# ESP32_WROOM32_E-DA_Sensor_Network_V1_0.net
KiCad netlist of a schematic drawn in EAGLE
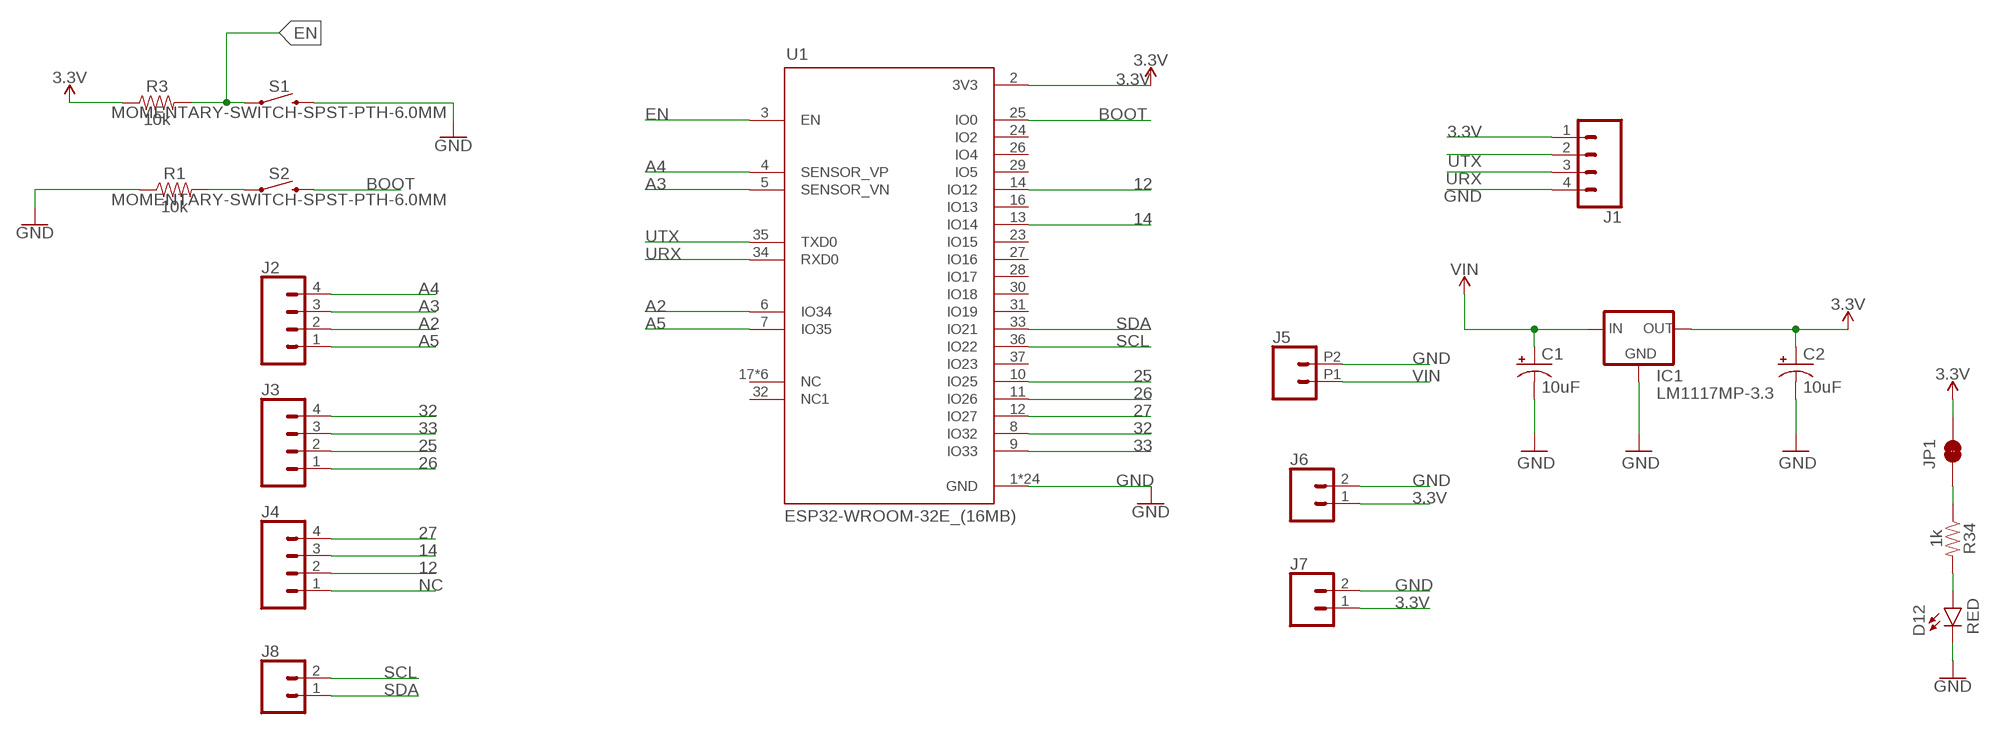
[diagram p0: schematic, sheet 1]

(export (version "E")
  (design (tool "Eeschema 10.0.6"))
  (components
    (comp (ref "C1")
      (value "10uF")
      (footprint "eagle-import:EIA3216")
      (libsource (lib "eagle-import") (part "10UF-TANT"))
    )
    (comp (ref "C2")
      (value "10uF")
      (footprint "eagle-import:EIA3216")
      (libsource (lib "eagle-import") (part "10UF-TANT"))
    )
    (comp (ref "D12")
      (value "RED")
      (footprint "eagle-import:LED-0603")
      (libsource (lib "eagle-import") (part "LED-RED0603"))
    )
    (comp (ref "IC1")
      (value "LM1117MP-3.3")
      (footprint "eagle-import:SOT223")
      (fields (field (name "MF") "Texas Instruments"))
      (libsource (lib "eagle-import") (part "LM1117?-MP3.3"))
    )
    (comp (ref "J1")
      (value "CONN_04")
      (footprint "eagle-import:1X04")
      (libsource (lib "eagle-import") (part "CONN_04"))
    )
    (comp (ref "J2")
      (value "CONN_04")
      (footprint "eagle-import:1X04")
      (libsource (lib "eagle-import") (part "CONN_04"))
    )
    (comp (ref "J3")
      (value "CONN_04")
      (footprint "eagle-import:1X04")
      (libsource (lib "eagle-import") (part "CONN_04"))
    )
    (comp (ref "J4")
      (value "CONN_04")
      (footprint "eagle-import:1X04")
      (libsource (lib "eagle-import") (part "CONN_04"))
    )
    (comp (ref "J5")
      (value "CONN_022.54MM_SCREWTERM")
      (footprint "eagle-import:1X02_2.54_SCREWTERM")
      (libsource (lib "eagle-import") (part "CONN_022.54MM_SCREWTERM"))
    )
    (comp (ref "J6")
      (value "CONN_021X02_NO_SILK")
      (footprint "eagle-import:1X02_NO_SILK")
      (libsource (lib "eagle-import") (part "CONN_021X02_NO_SILK"))
    )
    (comp (ref "J7")
      (value "CONN_021X02_NO_SILK")
      (footprint "eagle-import:1X02_NO_SILK")
      (libsource (lib "eagle-import") (part "CONN_021X02_NO_SILK"))
    )
    (comp (ref "J8")
      (value "CONN_02")
      (footprint "eagle-import:1X02")
      (libsource (lib "eagle-import") (part "CONN_02"))
    )
    (comp (ref "JP1")
      (value "JUMPER-SMT_2_NC_TRACE_SILK")
      (footprint "eagle-import:SMT-JUMPER_2_NC_TRACE_SILK")
      (libsource (lib "eagle-import") (part "JUMPER-SMT_2_NC_TRACE_SILK"))
    )
    (comp (ref "R1")
      (value "10k")
      (footprint "eagle-import:0603")
      (libsource (lib "eagle-import") (part "10KOHM-0603-1/10W-1%"))
    )
    (comp (ref "R3")
      (value "10k")
      (footprint "eagle-import:0603")
      (libsource (lib "eagle-import") (part "10KOHM-0603-1/10W-1%"))
    )
    (comp (ref "R34")
      (value "1k")
      (footprint "eagle-import:0402-TIGHT")
      (libsource (lib "eagle-import") (part "1KOHM-0402T-1/16W-1%"))
    )
    (comp (ref "S1")
      (value "MOMENTARY-SWITCH-SPST-PTH-6.0MM")
      (footprint "eagle-import:TACTILE_SWITCH_PTH_6.0MM")
      (libsource (lib "eagle-import") (part "MOMENTARY-SWITCH-SPST-PTH-6.0MM"))
    )
    (comp (ref "S2")
      (value "MOMENTARY-SWITCH-SPST-PTH-6.0MM")
      (footprint "eagle-import:TACTILE_SWITCH_PTH_6.0MM")
      (libsource (lib "eagle-import") (part "MOMENTARY-SWITCH-SPST-PTH-6.0MM"))
    )
    (comp (ref "U1")
      (value "ESP32-WROOM-32E_(16MB)")
      (footprint "eagle-import:MODULE_ESP32-WROOM-32E_(16MB)")
      (fields (field (name "MF") "Espressif Systems") (field (name "MP") "ESP32-WROOM-32E (16MB)"))
      (libsource (lib "eagle-import") (part "ESP32-WROOM-32E_(16MB)"))
    )
  )
  (nets
    (net (code "1") (name "/12") (class "Default")
      (node (ref "J4") (pin "2") (pinfunction "2_2") (pintype "passive"))
      (node (ref "U1") (pin "14") (pinfunction "IO12_14") (pintype "bidirectional"))
    )
    (net (code "2") (name "/14") (class "Default")
      (node (ref "J4") (pin "3") (pinfunction "3_3") (pintype "passive"))
      (node (ref "U1") (pin "13") (pinfunction "IO14_13") (pintype "bidirectional"))
    )
    (net (code "3") (name "/25") (class "Default")
      (node (ref "J3") (pin "2") (pinfunction "2_2") (pintype "passive"))
      (node (ref "U1") (pin "10") (pinfunction "IO25_10") (pintype "bidirectional"))
    )
    (net (code "4") (name "/26") (class "Default")
      (node (ref "J3") (pin "1") (pinfunction "1_1") (pintype "passive"))
      (node (ref "U1") (pin "11") (pinfunction "IO26_11") (pintype "bidirectional"))
    )
    (net (code "5") (name "/27") (class "Default")
      (node (ref "J4") (pin "4") (pinfunction "4_4") (pintype "passive"))
      (node (ref "U1") (pin "12") (pinfunction "IO27_12") (pintype "bidirectional"))
    )
    (net (code "6") (name "/32") (class "Default")
      (node (ref "J3") (pin "4") (pinfunction "4_4") (pintype "passive"))
      (node (ref "U1") (pin "8") (pinfunction "IO32_8") (pintype "bidirectional"))
    )
    (net (code "7") (name "/33") (class "Default")
      (node (ref "J3") (pin "3") (pinfunction "3_3") (pintype "passive"))
      (node (ref "U1") (pin "9") (pinfunction "IO33_9") (pintype "bidirectional"))
    )
    (net (code "8") (name "/A2") (class "Default")
      (node (ref "J2") (pin "2") (pinfunction "2_2") (pintype "passive"))
      (node (ref "U1") (pin "6") (pinfunction "IO34_6") (pintype "input"))
    )
    (net (code "9") (name "/A3") (class "Default")
      (node (ref "J2") (pin "3") (pinfunction "3_3") (pintype "passive"))
      (node (ref "U1") (pin "5") (pinfunction "SENSOR_VN_5") (pintype "input"))
    )
    (net (code "10") (name "/A4") (class "Default")
      (node (ref "J2") (pin "4") (pinfunction "4_4") (pintype "passive"))
      (node (ref "U1") (pin "4") (pinfunction "SENSOR_VP_4") (pintype "input"))
    )
    (net (code "11") (name "/A5") (class "Default")
      (node (ref "J2") (pin "1") (pinfunction "1_1") (pintype "passive"))
      (node (ref "U1") (pin "7") (pinfunction "IO35_7") (pintype "input"))
    )
    (net (code "12") (name "/BOOT") (class "Default")
      (node (ref "S2") (pin "3") (pinfunction "2_3") (pintype "passive"))
      (node (ref "U1") (pin "25") (pinfunction "IO0_25") (pintype "bidirectional"))
    )
    (net (code "13") (name "/NC") (class "Default")
      (node (ref "J4") (pin "1") (pinfunction "1_1") (pintype "passive"))
    )
    (net (code "14") (name "/SCL") (class "Default")
      (node (ref "J8") (pin "2") (pinfunction "2_2") (pintype "passive"))
      (node (ref "U1") (pin "36") (pinfunction "IO22_36") (pintype "bidirectional"))
    )
    (net (code "15") (name "/SDA") (class "Default")
      (node (ref "J8") (pin "1") (pinfunction "1_1") (pintype "passive"))
      (node (ref "U1") (pin "33") (pinfunction "IO21_33") (pintype "bidirectional"))
    )
    (net (code "16") (name "/URX") (class "Default")
      (node (ref "J1") (pin "3") (pinfunction "3_3") (pintype "passive"))
      (node (ref "U1") (pin "34") (pinfunction "RXD0_34") (pintype "bidirectional"))
    )
    (net (code "17") (name "/UTX") (class "Default")
      (node (ref "J1") (pin "2") (pinfunction "2_2") (pintype "passive"))
      (node (ref "U1") (pin "35") (pinfunction "TXD0_35") (pintype "bidirectional"))
    )
    (net (code "18") (name "3.3V") (class "Default")
      (node (ref "C2") (pin "A") (pinfunction "+_A") (pintype "passive"))
      (node (ref "IC1") (pin "2") (pinfunction "OUT_2") (pintype "passive"))
      (node (ref "IC1") (pin "4") (pinfunction "OUT_4") (pintype "passive"))
      (node (ref "J1") (pin "1") (pinfunction "1_1") (pintype "passive"))
      (node (ref "J6") (pin "1") (pinfunction "1_1") (pintype "passive"))
      (node (ref "J7") (pin "1") (pinfunction "1_1") (pintype "passive"))
      (node (ref "JP1") (pin "2") (pinfunction "2_2") (pintype "passive"))
      (node (ref "R3") (pin "1") (pinfunction "1_1") (pintype "passive"))
      (node (ref "U1") (pin "2") (pinfunction "3V3_2") (pintype "power_in"))
    )
    (net (code "19") (name "EN") (class "Default")
      (node (ref "R3") (pin "2") (pinfunction "2_2") (pintype "passive"))
      (node (ref "S1") (pin "1") (pinfunction "1_1") (pintype "passive"))
      (node (ref "U1") (pin "3") (pinfunction "EN_3") (pintype "input"))
    )
    (net (code "20") (name "GND") (class "Default")
      (node (ref "C1") (pin "C") (pinfunction "-_C") (pintype "passive"))
      (node (ref "C2") (pin "C") (pinfunction "-_C") (pintype "passive"))
      (node (ref "D12") (pin "C") (pinfunction "C_C") (pintype "passive"))
      (node (ref "IC1") (pin "1") (pinfunction "GND_1") (pintype "input"))
      (node (ref "J1") (pin "4") (pinfunction "4_4") (pintype "passive"))
      (node (ref "J5") (pin "P2") (pinfunction "2_P2") (pintype "passive"))
      (node (ref "J6") (pin "2") (pinfunction "2_2") (pintype "passive"))
      (node (ref "J7") (pin "2") (pinfunction "2_2") (pintype "passive"))
      (node (ref "R1") (pin "1") (pinfunction "1_1") (pintype "passive"))
      (node (ref "S1") (pin "3") (pinfunction "2_3") (pintype "passive"))
      (node (ref "U1") (pin "1") (pinfunction "GND_1") (pintype "power_in"))
      (node (ref "U1") (pin "15") (pinfunction "GND_15") (pintype "power_in"))
      (node (ref "U1") (pin "38") (pinfunction "GND_38") (pintype "power_in"))
      (node (ref "U1") (pin "39_1") (pinfunction "GND_39_1") (pintype "power_in"))
      (node (ref "U1") (pin "39_10") (pinfunction "GND_39_10") (pintype "power_in"))
      (node (ref "U1") (pin "39_11") (pinfunction "GND_39_11") (pintype "power_in"))
      (node (ref "U1") (pin "39_12") (pinfunction "GND_39_12") (pintype "power_in"))
      (node (ref "U1") (pin "39_13") (pinfunction "GND_39_13") (pintype "power_in"))
      (node (ref "U1") (pin "39_14") (pinfunction "GND_39_14") (pintype "power_in"))
      (node (ref "U1") (pin "39_15") (pinfunction "GND_39_15") (pintype "power_in"))
      (node (ref "U1") (pin "39_16") (pinfunction "GND_39_16") (pintype "power_in"))
      (node (ref "U1") (pin "39_17") (pinfunction "GND_39_17") (pintype "power_in"))
      (node (ref "U1") (pin "39_18") (pinfunction "GND_39_18") (pintype "power_in"))
      (node (ref "U1") (pin "39_19") (pinfunction "GND_39_19") (pintype "power_in"))
      (node (ref "U1") (pin "39_2") (pinfunction "GND_39_2") (pintype "power_in"))
      (node (ref "U1") (pin "39_20") (pinfunction "GND_39_20") (pintype "power_in"))
      (node (ref "U1") (pin "39_21") (pinfunction "GND_39_21") (pintype "power_in"))
      (node (ref "U1") (pin "39_3") (pinfunction "GND_39_3") (pintype "power_in"))
      (node (ref "U1") (pin "39_4") (pinfunction "GND_39_4") (pintype "power_in"))
      (node (ref "U1") (pin "39_5") (pinfunction "GND_39_5") (pintype "power_in"))
      (node (ref "U1") (pin "39_6") (pinfunction "GND_39_6") (pintype "power_in"))
      (node (ref "U1") (pin "39_7") (pinfunction "GND_39_7") (pintype "power_in"))
      (node (ref "U1") (pin "39_8") (pinfunction "GND_39_8") (pintype "power_in"))
      (node (ref "U1") (pin "39_9") (pinfunction "GND_39_9") (pintype "power_in"))
    )
    (net (code "21") (name "Net-(D12-PadA)") (class "Default")
      (node (ref "D12") (pin "A") (pinfunction "A_A") (pintype "passive"))
      (node (ref "R34") (pin "2") (pinfunction "2_2") (pintype "passive"))
    )
    (net (code "22") (name "Net-(JP1-Pad1)") (class "Default")
      (node (ref "JP1") (pin "1") (pinfunction "1_1") (pintype "passive"))
      (node (ref "R34") (pin "1") (pinfunction "1_1") (pintype "passive"))
    )
    (net (code "23") (name "Net-(R1-Pad2)") (class "Default")
      (node (ref "R1") (pin "2") (pinfunction "2_2") (pintype "passive"))
      (node (ref "S2") (pin "1") (pinfunction "1_1") (pintype "passive"))
    )
    (net (code "24") (name "VIN") (class "Default")
      (node (ref "C1") (pin "A") (pinfunction "+_A") (pintype "passive"))
      (node (ref "IC1") (pin "3") (pinfunction "IN_3") (pintype "input"))
      (node (ref "J5") (pin "P1") (pinfunction "1_P1") (pintype "passive"))
    )
    (net (code "25") (name "unconnected-(U1-IO2-Pad24)") (class "Default")
      (node (ref "U1") (pin "24") (pinfunction "IO2_24") (pintype "bidirectional"))
    )
    (net (code "26") (name "unconnected-(U1-IO4-Pad26)") (class "Default")
      (node (ref "U1") (pin "26") (pinfunction "IO4_26") (pintype "bidirectional"))
    )
    (net (code "27") (name "unconnected-(U1-IO5-Pad29)") (class "Default")
      (node (ref "U1") (pin "29") (pinfunction "IO5_29") (pintype "bidirectional"))
    )
    (net (code "28") (name "unconnected-(U1-IO13-Pad16)") (class "Default")
      (node (ref "U1") (pin "16") (pinfunction "IO13_16") (pintype "bidirectional"))
    )
    (net (code "29") (name "unconnected-(U1-IO15-Pad23)") (class "Default")
      (node (ref "U1") (pin "23") (pinfunction "IO15_23") (pintype "bidirectional"))
    )
    (net (code "30") (name "unconnected-(U1-IO16-Pad27)") (class "Default")
      (node (ref "U1") (pin "27") (pinfunction "IO16_27") (pintype "bidirectional"))
    )
    (net (code "31") (name "unconnected-(U1-IO17-Pad28)") (class "Default")
      (node (ref "U1") (pin "28") (pinfunction "IO17_28") (pintype "bidirectional"))
    )
    (net (code "32") (name "unconnected-(U1-IO18-Pad30)") (class "Default")
      (node (ref "U1") (pin "30") (pinfunction "IO18_30") (pintype "bidirectional"))
    )
    (net (code "33") (name "unconnected-(U1-IO19-Pad31)") (class "Default")
      (node (ref "U1") (pin "31") (pinfunction "IO19_31") (pintype "bidirectional"))
    )
    (net (code "34") (name "unconnected-(U1-IO23-Pad37)") (class "Default")
      (node (ref "U1") (pin "37") (pinfunction "IO23_37") (pintype "bidirectional"))
    )
    (net (code "35") (name "unconnected-(U1-NC-Pad17)") (class "Default")
      (node (ref "U1") (pin "17") (pinfunction "NC_17") (pintype "no_connect"))
    )
    (net (code "36") (name "unconnected-(U1-NC-Pad18)") (class "Default")
      (node (ref "U1") (pin "18") (pinfunction "NC_18") (pintype "no_connect"))
    )
    (net (code "37") (name "unconnected-(U1-NC-Pad19)") (class "Default")
      (node (ref "U1") (pin "19") (pinfunction "NC_19") (pintype "no_connect"))
    )
    (net (code "38") (name "unconnected-(U1-NC-Pad20)") (class "Default")
      (node (ref "U1") (pin "20") (pinfunction "NC_20") (pintype "no_connect"))
    )
    (net (code "39") (name "unconnected-(U1-NC-Pad21)") (class "Default")
      (node (ref "U1") (pin "21") (pinfunction "NC_21") (pintype "no_connect"))
    )
    (net (code "40") (name "unconnected-(U1-NC-Pad22)") (class "Default")
      (node (ref "U1") (pin "22") (pinfunction "NC_22") (pintype "no_connect"))
    )
    (net (code "41") (name "unconnected-(U1-NC1-Pad32)") (class "Default")
      (node (ref "U1") (pin "32") (pinfunction "NC1_32") (pintype "no_connect"))
    )
  )
)
